# encoder.net
KiCad netlist of a schematic drawn in Altium Designer
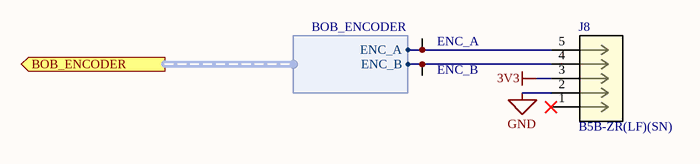
[diagram p0: encoder.SchDoc]

(export (version "E")
  (design (tool "Eeschema 10.0.6"))
  (components
    (comp (ref "ENC_A")
      (value "Test Point (Via)")
      (footprint "TP")
      (libsource (lib "AltiumLibraries") (part "Test Point (Via)"))
    )
    (comp (ref "ENC_B")
      (value "Test Point (Via)")
      (footprint "TP")
      (libsource (lib "AltiumLibraries") (part "Test Point (Via)"))
    )
    (comp (ref "J8")
      (value "B5B-ZR(LF)(SN)")
      (footprint "JST_B5B-ZR(LF)(SN)")
      (description "Connector Header Through Hole 5 position 0.059 (1.50mm)")
      (fields (field (name "MF") "JST Sales"))
      (libsource (lib "AltiumLibraries") (part "CN 5POS JST ZR"))
    )
  )
  (nets
    (net (code "3") (name "3V3") (class "Default")
      (node (ref "J8") (pin "3") (pinfunction "3_3") (pintype "passive"))
    )
    (net (code "4") (name "GND") (class "Default")
      (node (ref "J8") (pin "2") (pinfunction "2_2") (pintype "passive"))
    )
    (net (code "5") (name "Net-(ENC_A-Pad1)") (class "Default")
      (node (ref "ENC_A") (pin "1") (pinfunction "1_1") (pintype "passive"))
      (node (ref "J8") (pin "5") (pinfunction "5_5") (pintype "passive"))
    )
    (net (code "6") (name "Net-(ENC_B-Pad1)") (class "Default")
      (node (ref "ENC_B") (pin "1") (pinfunction "1_1") (pintype "passive"))
      (node (ref "J8") (pin "4") (pinfunction "4_4") (pintype "passive"))
    )
    (net (code "7") (name "unconnected-(J8-Pad1)") (class "Default")
      (node (ref "J8") (pin "1") (pinfunction "1_1") (pintype "passive+no_connect"))
    )
  )
)
